# ACme.net
KiCad netlist of a schematic drawn in EAGLE
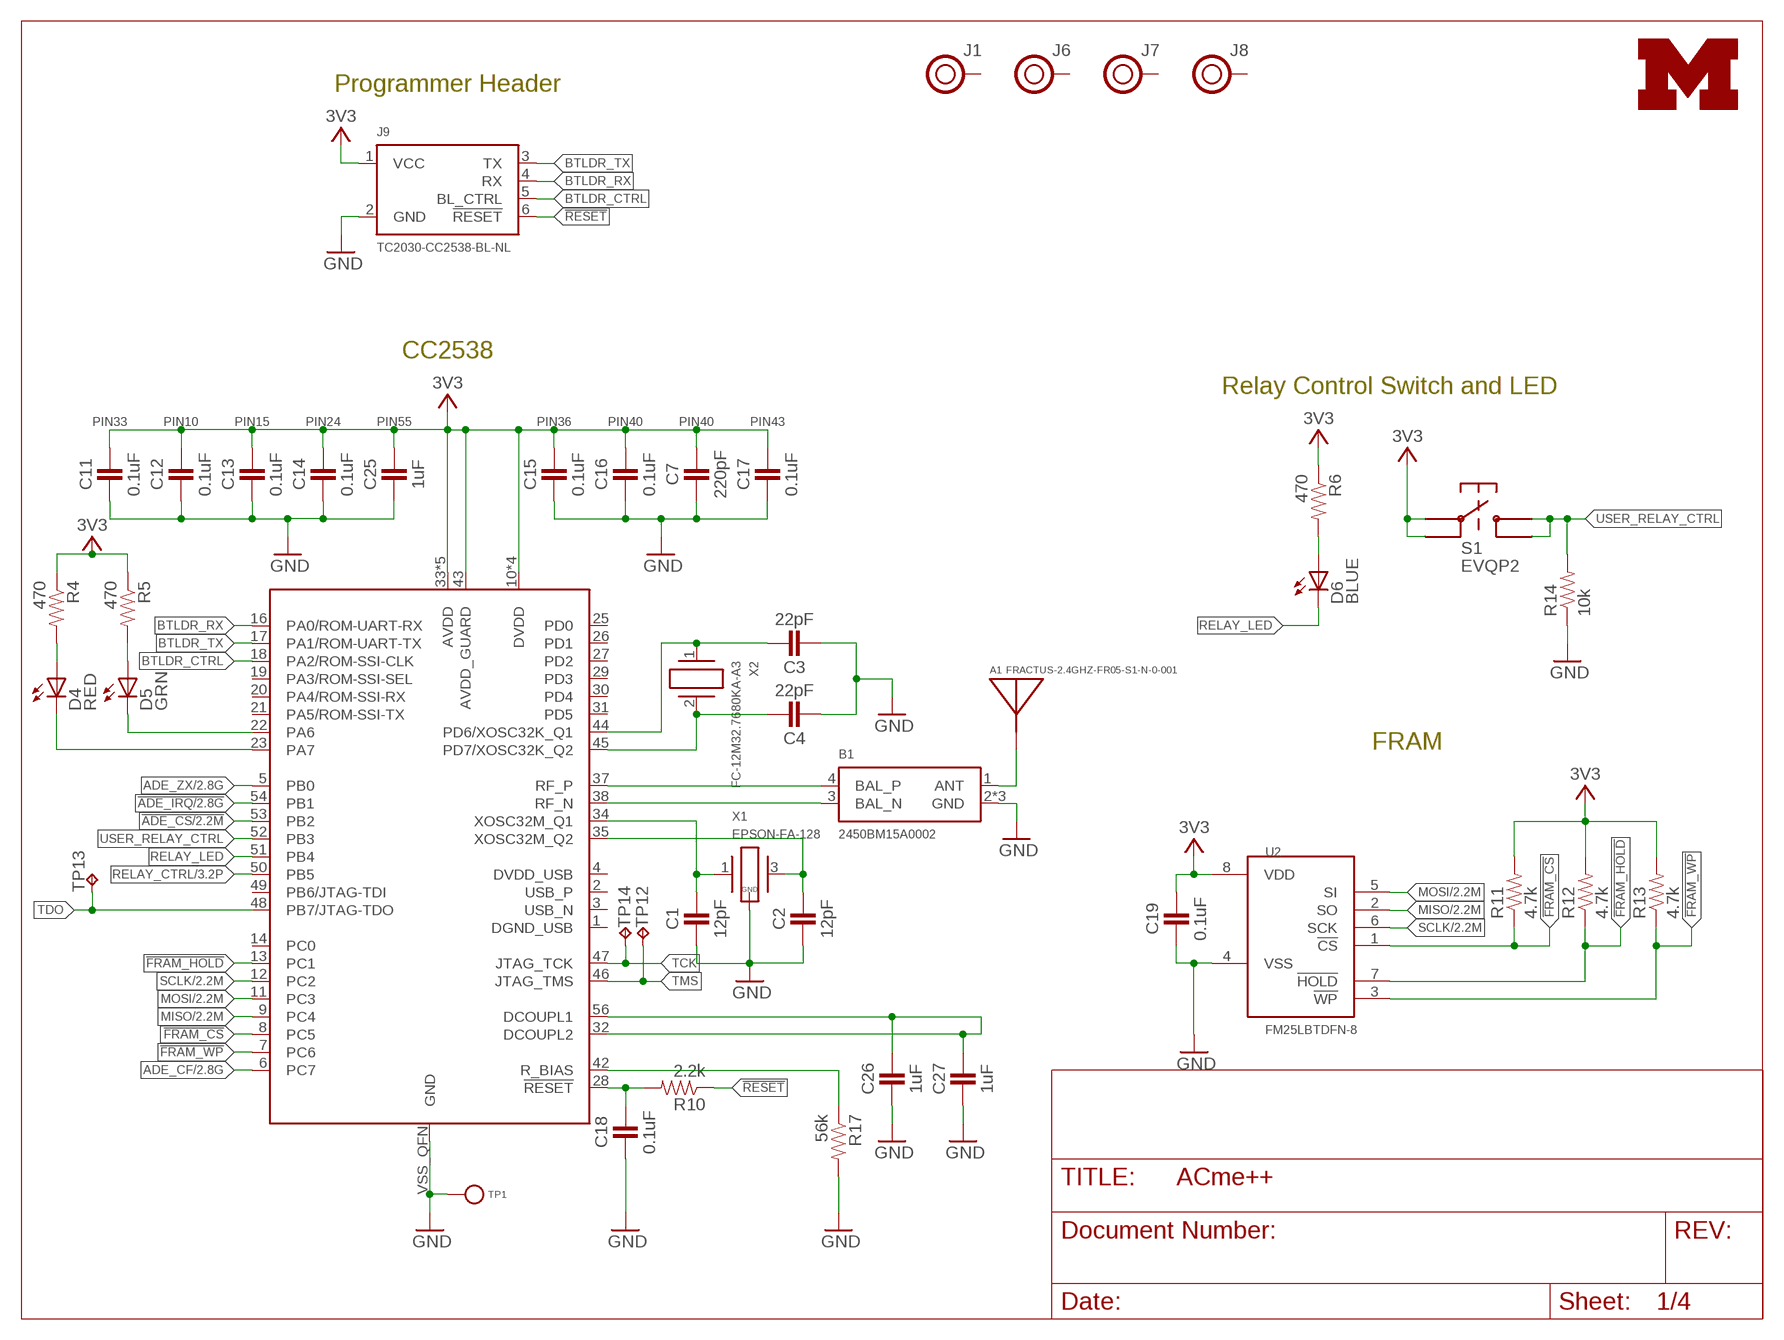
[diagram p0: schematic, sheet 1]
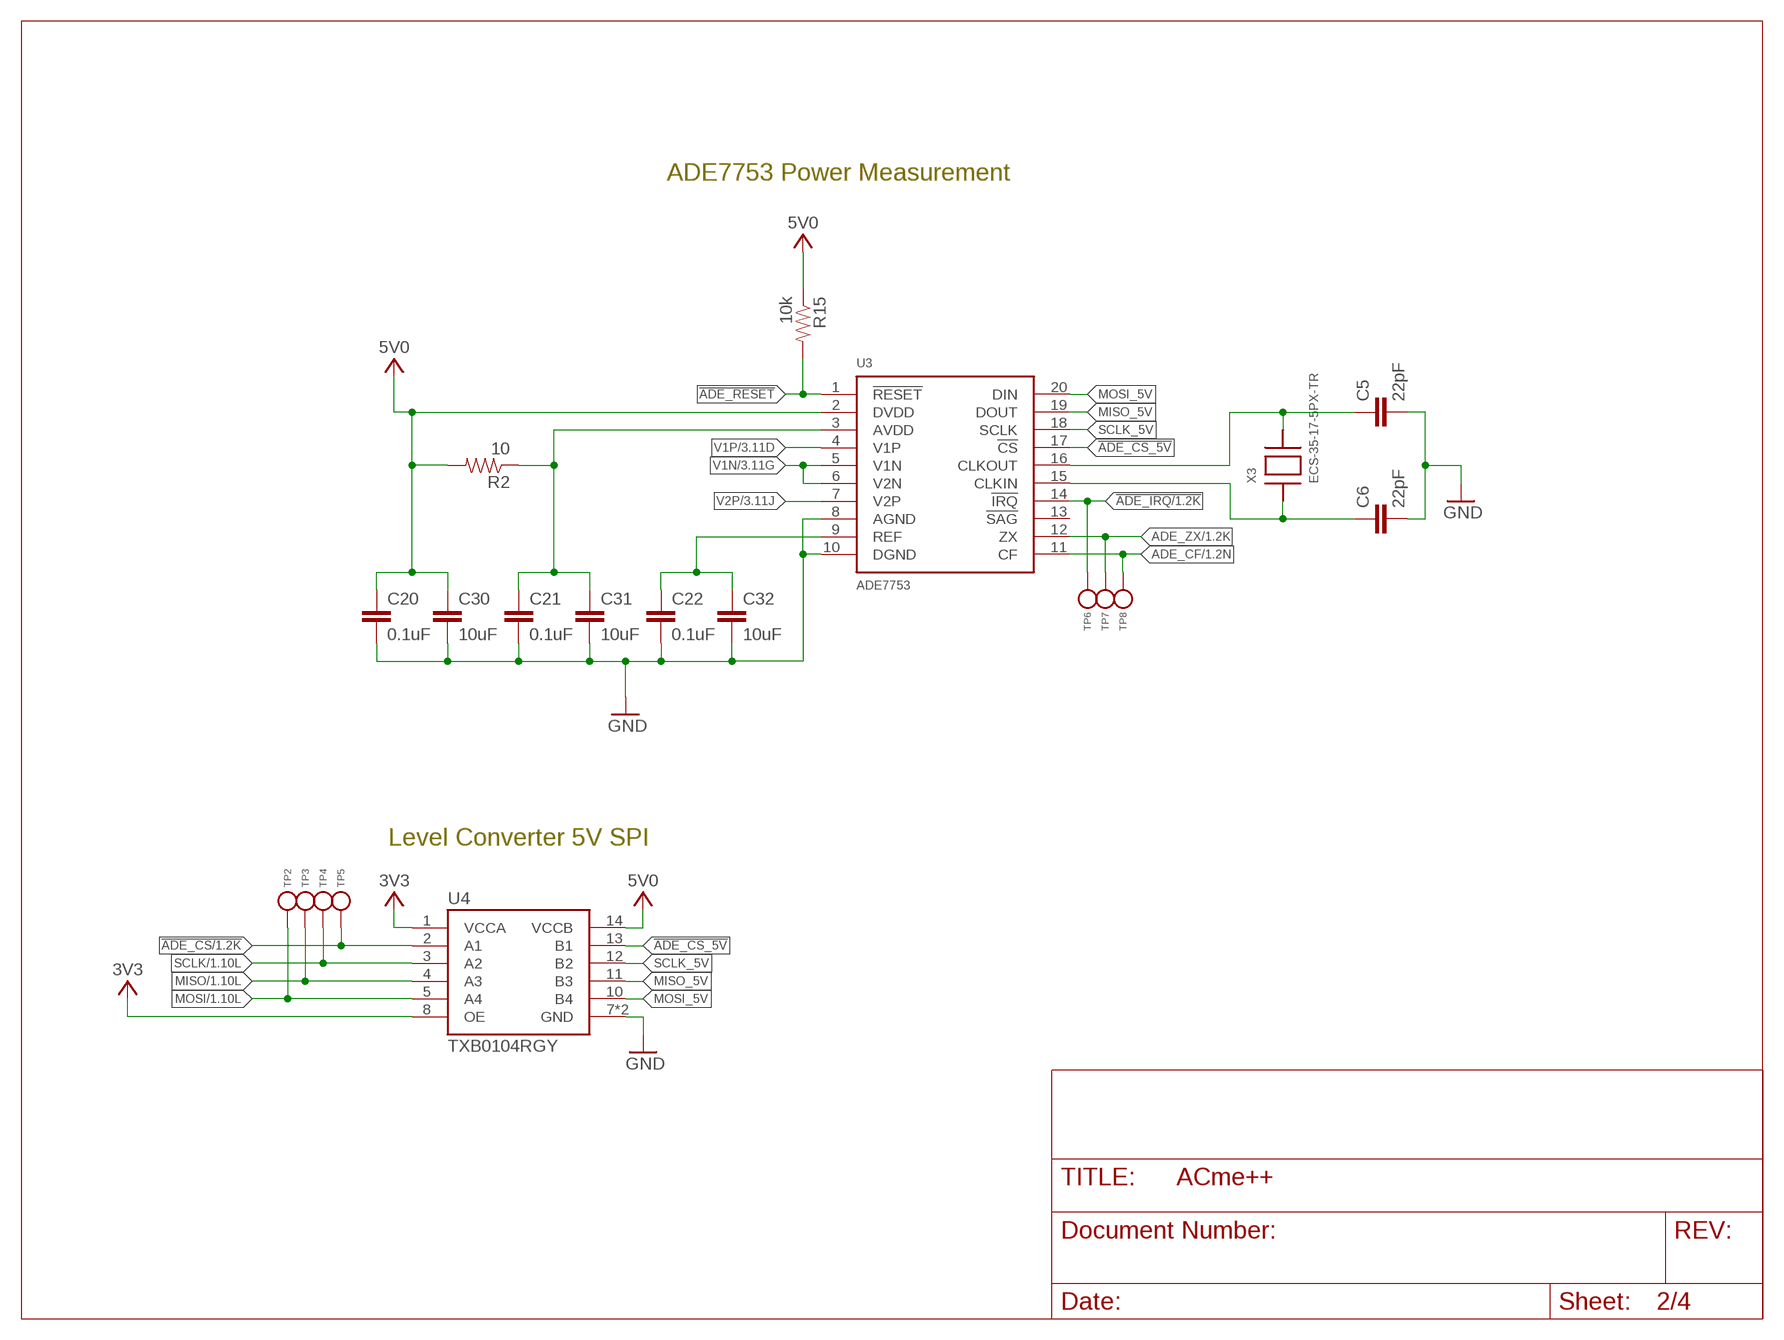
[diagram p1: schematic, sheet 2]
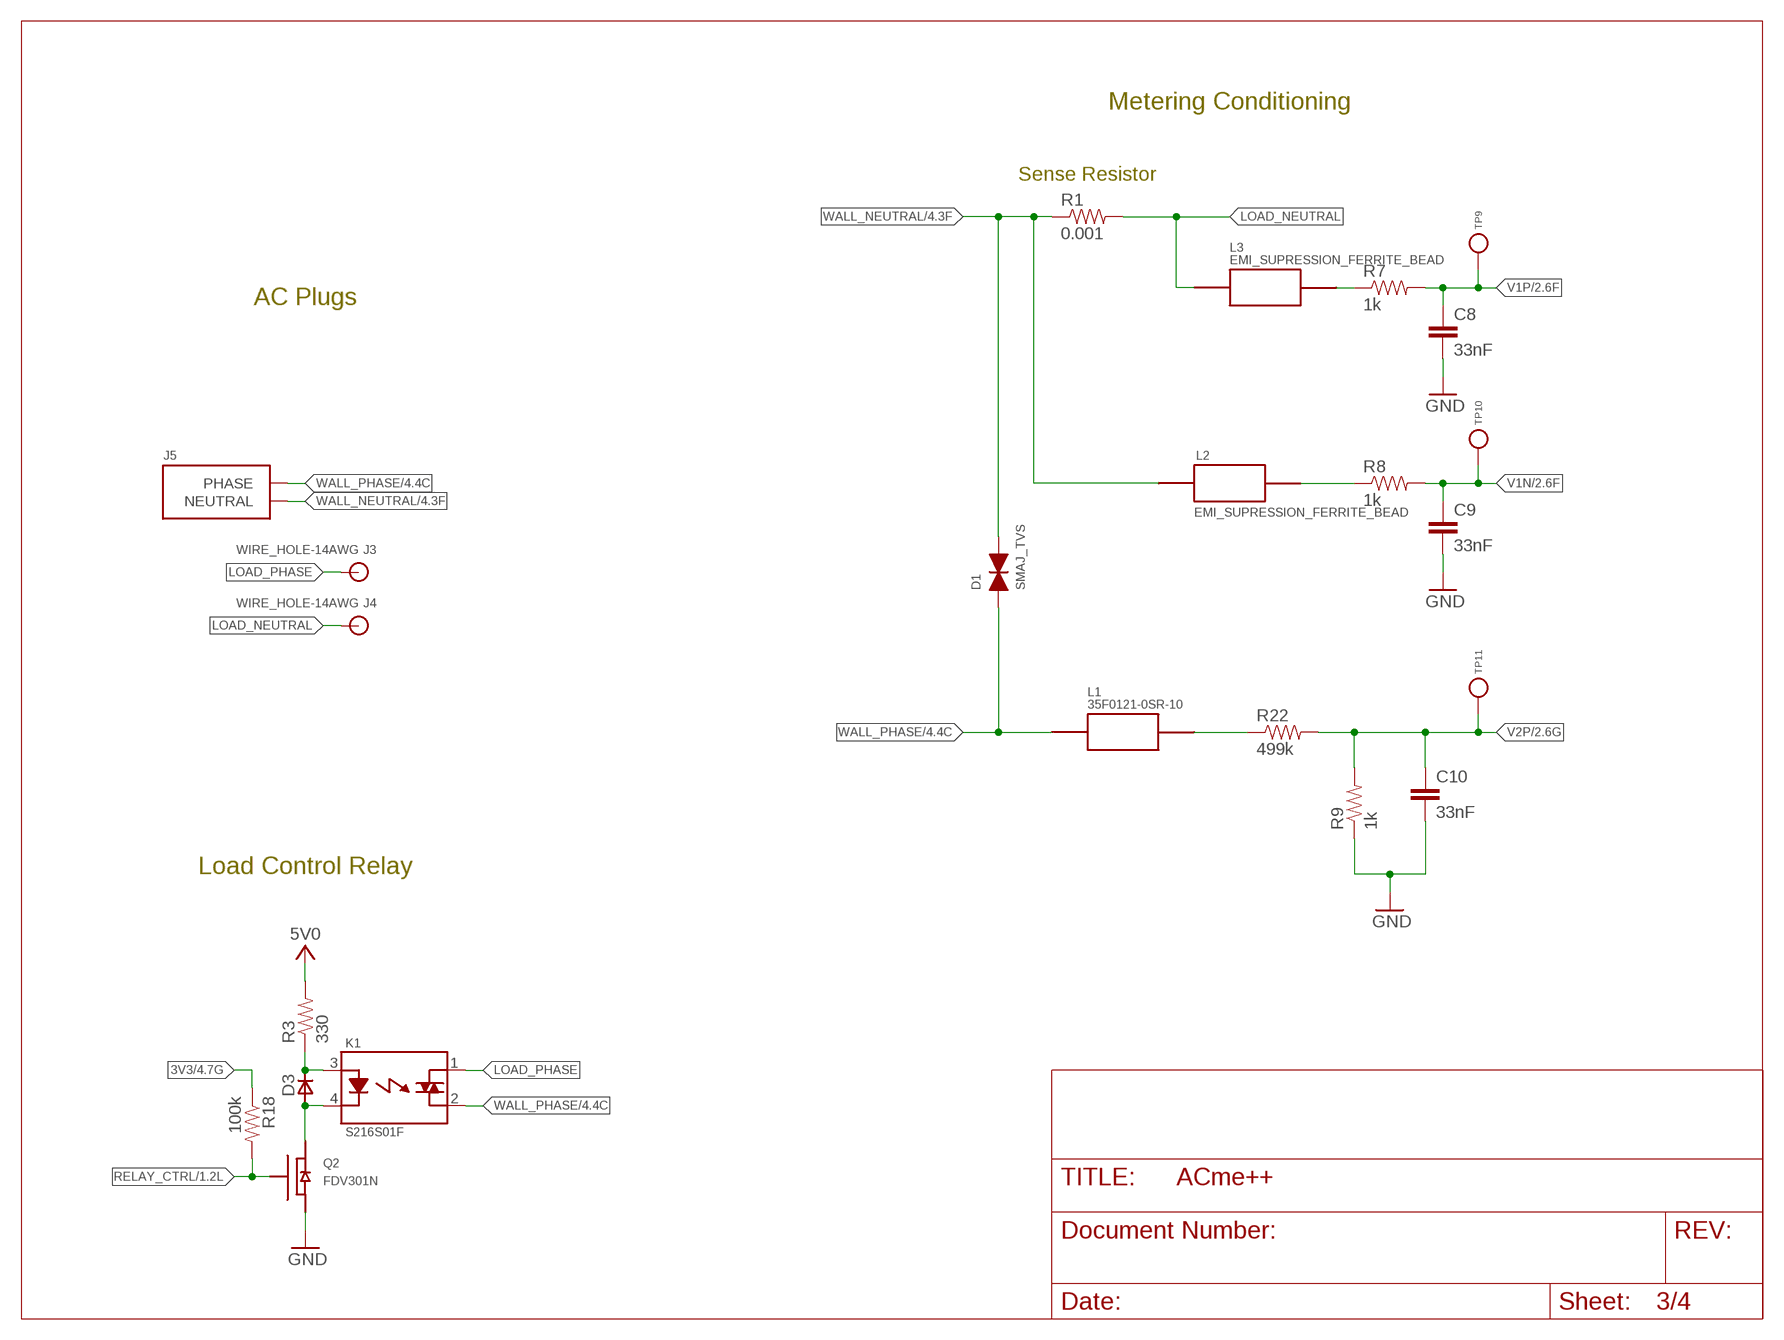
[diagram p2: schematic, sheet 3]
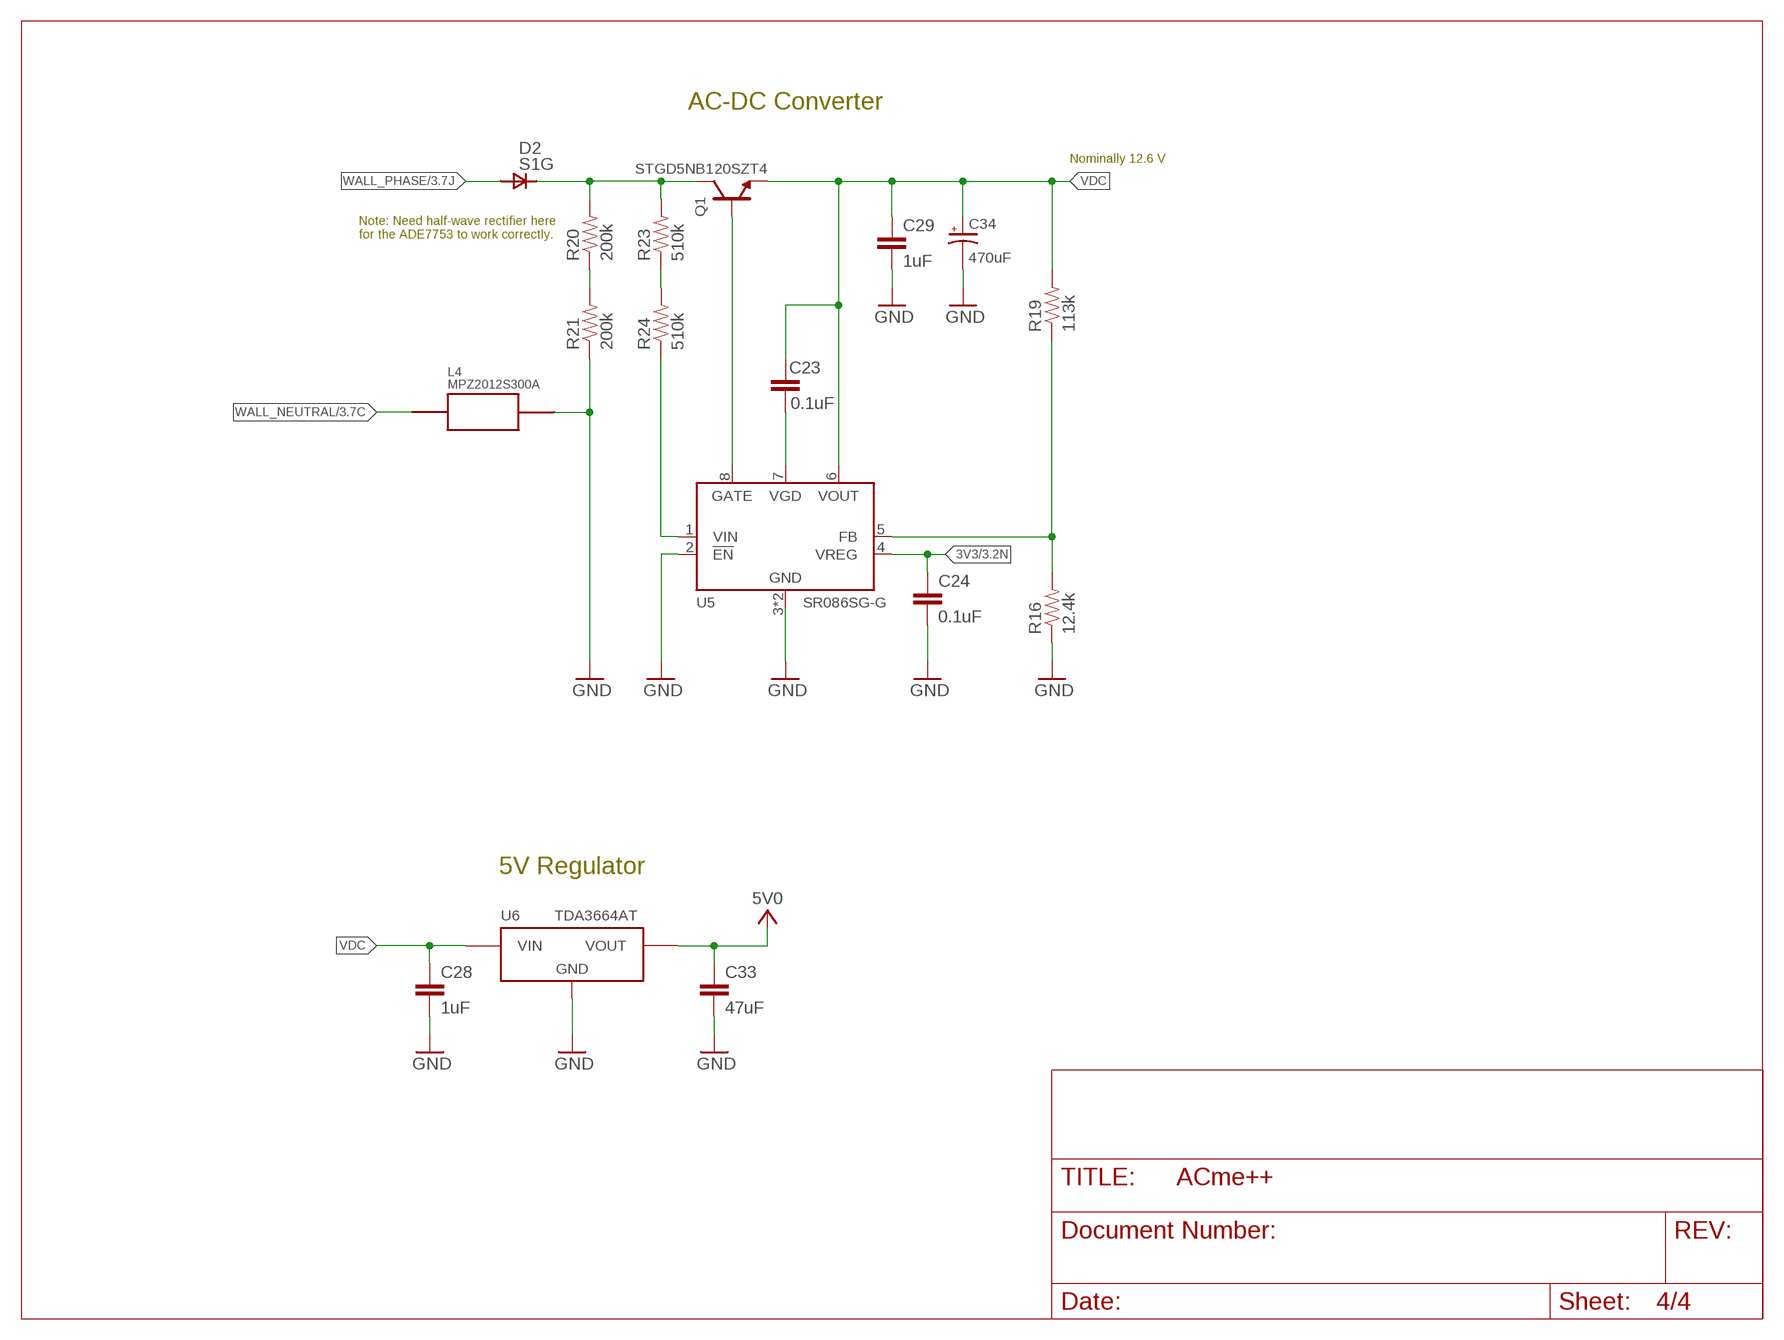
[diagram p3: schematic, sheet 4]

(export (version "E")
  (design (tool "Eeschema 10.0.6"))
  (components
    (comp (ref "A1")
      (value "FRACTUS-2.4GHZ-FR05-S1-N-0-001")
      (footprint "eagle-import:FRACTUS-ANTENNA-FR05-S1-N-0-001")
      (libsource (lib "eagle-import") (part "FRACTUS-2.4GHZ-FR05-S1-N-0-001"))
    )
    (comp (ref "B1")
      (value "2450BM15A0002")
      (footprint "eagle-import:2450BM")
      (libsource (lib "eagle-import") (part "2450BM15A0002"))
    )
    (comp (ref "C1")
      (value "12pF")
      (footprint "eagle-import:0402_CAP")
      (libsource (lib "eagle-import") (part "CAPACITOR"))
    )
    (comp (ref "C2")
      (value "12pF")
      (footprint "eagle-import:0402_CAP")
      (libsource (lib "eagle-import") (part "CAPACITOR"))
    )
    (comp (ref "C3")
      (value "22pF")
      (footprint "eagle-import:0402_CAP")
      (libsource (lib "eagle-import") (part "CAPACITOR"))
    )
    (comp (ref "C4")
      (value "22pF")
      (footprint "eagle-import:0402_CAP")
      (libsource (lib "eagle-import") (part "CAPACITOR"))
    )
    (comp (ref "C7")
      (value "220pF")
      (footprint "eagle-import:0402_CAP")
      (libsource (lib "eagle-import") (part "CAPACITOR"))
    )
    (comp (ref "C11")
      (value "0.1uF")
      (footprint "eagle-import:0402_CAP")
      (libsource (lib "eagle-import") (part "CAPACITOR"))
    )
    (comp (ref "C12")
      (value "0.1uF")
      (footprint "eagle-import:0402_CAP")
      (libsource (lib "eagle-import") (part "CAPACITOR"))
    )
    (comp (ref "C13")
      (value "0.1uF")
      (footprint "eagle-import:0402_CAP")
      (libsource (lib "eagle-import") (part "CAPACITOR"))
    )
    (comp (ref "C14")
      (value "0.1uF")
      (footprint "eagle-import:0402_CAP")
      (libsource (lib "eagle-import") (part "CAPACITOR"))
    )
    (comp (ref "C15")
      (value "0.1uF")
      (footprint "eagle-import:0402_CAP")
      (libsource (lib "eagle-import") (part "CAPACITOR"))
    )
    (comp (ref "C16")
      (value "0.1uF")
      (footprint "eagle-import:0402_CAP")
      (libsource (lib "eagle-import") (part "CAPACITOR"))
    )
    (comp (ref "C17")
      (value "0.1uF")
      (footprint "eagle-import:0402_CAP")
      (libsource (lib "eagle-import") (part "CAPACITOR"))
    )
    (comp (ref "C18")
      (value "0.1uF")
      (footprint "eagle-import:0402_CAP")
      (libsource (lib "eagle-import") (part "CAPACITOR"))
    )
    (comp (ref "C19")
      (value "0.1uF")
      (footprint "eagle-import:0402_CAP")
      (libsource (lib "eagle-import") (part "CAPACITOR"))
    )
    (comp (ref "C25")
      (value "1uF")
      (footprint "eagle-import:0402_CAP")
      (libsource (lib "eagle-import") (part "CAPACITOR"))
    )
    (comp (ref "C26")
      (value "1uF")
      (footprint "eagle-import:0402_CAP")
      (libsource (lib "eagle-import") (part "CAPACITOR"))
    )
    (comp (ref "C27")
      (value "1uF")
      (footprint "eagle-import:0402_CAP")
      (libsource (lib "eagle-import") (part "CAPACITOR"))
    )
    (comp (ref "D4")
      (value "RED")
      (footprint "eagle-import:LED-0603")
      (libsource (lib "eagle-import") (part "LED0603"))
    )
    (comp (ref "D5")
      (value "GRN")
      (footprint "eagle-import:LED-0603")
      (libsource (lib "eagle-import") (part "LED0603"))
    )
    (comp (ref "D6")
      (value "BLUE")
      (footprint "eagle-import:LED-0603")
      (libsource (lib "eagle-import") (part "LED0603"))
    )
    (comp (ref "J1")
      (value "HOLE")
      (footprint "eagle-import:HOLE-0.125")
      (libsource (lib "eagle-import") (part "HOLE"))
    )
    (comp (ref "J6")
      (value "HOLE")
      (footprint "eagle-import:HOLE-0.125")
      (libsource (lib "eagle-import") (part "HOLE"))
    )
    (comp (ref "J7")
      (value "HOLE")
      (footprint "eagle-import:HOLE-0.125")
      (libsource (lib "eagle-import") (part "HOLE"))
    )
    (comp (ref "J8")
      (value "HOLE")
      (footprint "eagle-import:HOLE-0.125")
      (libsource (lib "eagle-import") (part "HOLE"))
    )
    (comp (ref "J9")
      (value "TC2030-CC2538-BL-NL")
      (footprint "eagle-import:TC2030-IDC-NL")
      (libsource (lib "eagle-import") (part "TC2030-CC2538-BL-NL"))
    )
    (comp (ref "R4")
      (value "470")
      (footprint "eagle-import:0402_RES")
      (libsource (lib "eagle-import") (part "passives_RESISTOR"))
    )
    (comp (ref "R5")
      (value "470")
      (footprint "eagle-import:0402_RES")
      (libsource (lib "eagle-import") (part "passives_RESISTOR"))
    )
    (comp (ref "R6")
      (value "470")
      (footprint "eagle-import:0402_RES")
      (libsource (lib "eagle-import") (part "passives_RESISTOR"))
    )
    (comp (ref "R10")
      (value "2.2k")
      (footprint "eagle-import:0402_RES")
      (libsource (lib "eagle-import") (part "passives_RESISTOR"))
    )
    (comp (ref "R11")
      (value "4.7k")
      (footprint "eagle-import:0402_RES")
      (libsource (lib "eagle-import") (part "passives_RESISTOR"))
    )
    (comp (ref "R12")
      (value "4.7k")
      (footprint "eagle-import:0402_RES")
      (libsource (lib "eagle-import") (part "passives_RESISTOR"))
    )
    (comp (ref "R13")
      (value "4.7k")
      (footprint "eagle-import:0402_RES")
      (libsource (lib "eagle-import") (part "passives_RESISTOR"))
    )
    (comp (ref "R14")
      (value "10k")
      (footprint "eagle-import:0603-RES")
      (libsource (lib "eagle-import") (part "RESISTOR0603-RES"))
    )
    (comp (ref "R17")
      (value "56k")
      (footprint "eagle-import:0402_RES")
      (libsource (lib "eagle-import") (part "passives_RESISTOR"))
    )
    (comp (ref "S1")
      (value "EVQP2")
      (footprint "eagle-import:EVQP2")
      (libsource (lib "eagle-import") (part "EVQP2"))
    )
    (comp (ref "TP1")
      (value "TEST_POINT_0.040IN")
      (footprint "eagle-import:TESTPOINT_0.040IN")
      (libsource (lib "eagle-import") (part "TEST_POINT_0.040IN"))
    )
    (comp (ref "TP12")
      (value "TPTP09SQ")
      (footprint "eagle-import:TP09SQ")
      (libsource (lib "eagle-import") (part "TPTP09SQ"))
    )
    (comp (ref "TP13")
      (value "TPTP09SQ")
      (footprint "eagle-import:TP09SQ")
      (libsource (lib "eagle-import") (part "TPTP09SQ"))
    )
    (comp (ref "TP14")
      (value "TPTP09SQ")
      (footprint "eagle-import:TP09SQ")
      (libsource (lib "eagle-import") (part "TPTP09SQ"))
    )
    (comp (ref "U$3")
      (value "UMICH_SOLID_MEDIUM")
      (footprint "eagle-import:UMICH_SOLID_200MIL")
      (libsource (lib "eagle-import") (part "UMICH_SOLID_MEDIUM"))
    )
    (comp (ref "U1")
      (value "CC2538")
      (footprint "eagle-import:S-PVQFN-N56")
      (libsource (lib "eagle-import") (part "CC2538"))
    )
    (comp (ref "U2")
      (value "FM25LBTDFN-8")
      (footprint "eagle-import:TDFN-8")
      (libsource (lib "eagle-import") (part "FM25LBTDFN-8"))
    )
    (comp (ref "X1")
      (value "EPSON-FA-128")
      (footprint "eagle-import:FA-128")
      (libsource (lib "eagle-import") (part "EPSON-FA-128"))
    )
    (comp (ref "X2")
      (value "FC-12M32.7680KA-A3")
      (footprint "eagle-import:FC-12M")
      (libsource (lib "eagle-import") (part "FC-12M32.7680KA-A3"))
    )
    (comp (ref "C5")
      (value "22pF")
      (footprint "eagle-import:0603-CAP")
      (libsource (lib "eagle-import") (part "CAP0603-CAP"))
    )
    (comp (ref "C6")
      (value "22pF")
      (footprint "eagle-import:0603-CAP")
      (libsource (lib "eagle-import") (part "CAP0603-CAP"))
    )
    (comp (ref "C20")
      (value "0.1uF")
      (footprint "eagle-import:0603-CAP")
      (libsource (lib "eagle-import") (part "CAP0603-CAP"))
    )
    (comp (ref "C21")
      (value "0.1uF")
      (footprint "eagle-import:0603-CAP")
      (libsource (lib "eagle-import") (part "CAP0603-CAP"))
    )
    (comp (ref "C22")
      (value "0.1uF")
      (footprint "eagle-import:0603-CAP")
      (libsource (lib "eagle-import") (part "CAP0603-CAP"))
    )
    (comp (ref "C30")
      (value "10uF")
      (footprint "eagle-import:0603-CAP")
      (libsource (lib "eagle-import") (part "CAP0603-CAP"))
    )
    (comp (ref "C31")
      (value "10uF")
      (footprint "eagle-import:0603-CAP")
      (libsource (lib "eagle-import") (part "CAP0603-CAP"))
    )
    (comp (ref "C32")
      (value "10uF")
      (footprint "eagle-import:0603-CAP")
      (libsource (lib "eagle-import") (part "CAP0603-CAP"))
    )
    (comp (ref "R2")
      (value "10")
      (footprint "eagle-import:0603-RES")
      (libsource (lib "eagle-import") (part "RESISTOR0603-RES"))
    )
    (comp (ref "R15")
      (value "10k")
      (footprint "eagle-import:0603-RES")
      (libsource (lib "eagle-import") (part "RESISTOR0603-RES"))
    )
    (comp (ref "TP2")
      (value "TEST_POINT_0.040IN")
      (footprint "eagle-import:TESTPOINT_0.040IN")
      (libsource (lib "eagle-import") (part "TEST_POINT_0.040IN"))
    )
    (comp (ref "TP3")
      (value "TEST_POINT_0.040IN")
      (footprint "eagle-import:TESTPOINT_0.040IN")
      (libsource (lib "eagle-import") (part "TEST_POINT_0.040IN"))
    )
    (comp (ref "TP4")
      (value "TEST_POINT_0.040IN")
      (footprint "eagle-import:TESTPOINT_0.040IN")
      (libsource (lib "eagle-import") (part "TEST_POINT_0.040IN"))
    )
    (comp (ref "TP5")
      (value "TEST_POINT_0.040IN")
      (footprint "eagle-import:TESTPOINT_0.040IN")
      (libsource (lib "eagle-import") (part "TEST_POINT_0.040IN"))
    )
    (comp (ref "TP6")
      (value "TEST_POINT_0.040IN")
      (footprint "eagle-import:TESTPOINT_0.040IN")
      (libsource (lib "eagle-import") (part "TEST_POINT_0.040IN"))
    )
    (comp (ref "TP7")
      (value "TEST_POINT_0.040IN")
      (footprint "eagle-import:TESTPOINT_0.040IN")
      (libsource (lib "eagle-import") (part "TEST_POINT_0.040IN"))
    )
    (comp (ref "TP8")
      (value "TEST_POINT_0.040IN")
      (footprint "eagle-import:TESTPOINT_0.040IN")
      (libsource (lib "eagle-import") (part "TEST_POINT_0.040IN"))
    )
    (comp (ref "U3")
      (value "ADE7753")
      (footprint "eagle-import:SSOP-20")
      (fields (field (name "MOUSER") " 584-ADE7753ARSZR "))
      (libsource (lib "eagle-import") (part "ADE7753"))
    )
    (comp (ref "U4")
      (value "TXB0104RGY")
      (footprint "eagle-import:S-PVQFN-N14")
      (libsource (lib "eagle-import") (part "TXB0104RGY"))
    )
    (comp (ref "X3")
      (value "ECS-35-17-5PX-TR")
      (footprint "eagle-import:CSM-7X")
      (libsource (lib "eagle-import") (part "ECS-35-17-5PX-TR"))
    )
    (comp (ref "C23")
      (value "0.1uF")
      (footprint "eagle-import:0603-CAP")
      (libsource (lib "eagle-import") (part "CAP0603-CAP"))
    )
    (comp (ref "C24")
      (value "0.1uF")
      (footprint "eagle-import:0603-CAP")
      (libsource (lib "eagle-import") (part "CAP0603-CAP"))
    )
    (comp (ref "C28")
      (value "1uF")
      (footprint "eagle-import:0603-CAP")
      (libsource (lib "eagle-import") (part "CAP0603-CAP"))
    )
    (comp (ref "C29")
      (value "1uF")
      (footprint "eagle-import:1206")
      (libsource (lib "eagle-import") (part "CAP1206"))
    )
    (comp (ref "C33")
      (value "47uF")
      (footprint "eagle-import:1206")
      (libsource (lib "eagle-import") (part "CAP1206"))
    )
    (comp (ref "C34")
      (value "470uF")
      (footprint "eagle-import:CAP_SM_10MM")
      (libsource (lib "eagle-import") (part "CAP_EEE-FP1E471AP"))
    )
    (comp (ref "D2")
      (value "S1G")
      (footprint "eagle-import:DO-214AC")
      (libsource (lib "eagle-import") (part "S1G"))
    )
    (comp (ref "L4")
      (value "MPZ2012S300A")
      (footprint "eagle-import:0805_RESISTOR")
      (libsource (lib "eagle-import") (part "MPZ2012S300A"))
    )
    (comp (ref "Q1")
      (value "STGD5NB120SZT4")
      (footprint "eagle-import:DPAK")
      (libsource (lib "eagle-import") (part "STGD5NB120SZT4"))
    )
    (comp (ref "R16")
      (value "12.4k")
      (footprint "eagle-import:0603-RES")
      (libsource (lib "eagle-import") (part "SparkFun-Resistors_RESISTOR0603-RES"))
    )
    (comp (ref "R19")
      (value "113k")
      (footprint "eagle-import:0603-RES")
      (libsource (lib "eagle-import") (part "SparkFun-Resistors_RESISTOR0603-RES"))
    )
    (comp (ref "R20")
      (value "200k")
      (footprint "eagle-import:1206")
      (libsource (lib "eagle-import") (part "SparkFun-Resistors_RESISTOR1206"))
    )
    (comp (ref "R21")
      (value "200k")
      (footprint "eagle-import:1206")
      (libsource (lib "eagle-import") (part "SparkFun-Resistors_RESISTOR1206"))
    )
    (comp (ref "R23")
      (value "510k")
      (footprint "eagle-import:1206")
      (libsource (lib "eagle-import") (part "SparkFun-Resistors_RESISTOR1206"))
    )
    (comp (ref "R24")
      (value "510k")
      (footprint "eagle-import:1206")
      (libsource (lib "eagle-import") (part "SparkFun-Resistors_RESISTOR1206"))
    )
    (comp (ref "U5")
      (value "SR086SG-G")
      (footprint "eagle-import:SR086")
      (libsource (lib "eagle-import") (part "SR086SG-G"))
    )
    (comp (ref "U6")
      (value "TDA3664AT")
      (footprint "eagle-import:SOIC_8")
      (libsource (lib "eagle-import") (part "TDA3664AT"))
    )
    (comp (ref "C8")
      (value "33nF")
      (footprint "eagle-import:0805")
      (libsource (lib "eagle-import") (part "CAP0805"))
    )
    (comp (ref "C9")
      (value "33nF")
      (footprint "eagle-import:0805")
      (libsource (lib "eagle-import") (part "CAP0805"))
    )
    (comp (ref "C10")
      (value "33nF")
      (footprint "eagle-import:0805")
      (libsource (lib "eagle-import") (part "CAP0805"))
    )
    (comp (ref "D1")
      (value "SMAJ_TVS")
      (footprint "eagle-import:DO214_TVS")
      (libsource (lib "eagle-import") (part "SMAJ_TVS"))
    )
    (comp (ref "D3")
      (value "DIODE_MMBD914")
      (footprint "eagle-import:SOT-23")
      (libsource (lib "eagle-import") (part "DIODE_MMBD914"))
    )
    (comp (ref "J3")
      (value "WIRE_HOLE-14AWG")
      (footprint "eagle-import:WIRE_HOLE-14AWG")
      (libsource (lib "eagle-import") (part "WIRE_HOLE-14AWG"))
    )
    (comp (ref "J4")
      (value "WIRE_HOLE-14AWG")
      (footprint "eagle-import:WIRE_HOLE-14AWG")
      (libsource (lib "eagle-import") (part "WIRE_HOLE-14AWG"))
    )
    (comp (ref "J5")
      (value "AC-PLUG-2")
      (footprint "eagle-import:AC_MALE_PINS_2")
      (libsource (lib "eagle-import") (part "AC-PLUG-2"))
    )
    (comp (ref "K1")
      (value "S216S01F")
      (footprint "eagle-import:RELAY_SX16S0X")
      (libsource (lib "eagle-import") (part "S216S01F"))
    )
    (comp (ref "L1")
      (value "35F0121-0SR-10")
      (footprint "eagle-import:35F0102")
      (libsource (lib "eagle-import") (part "35F0121-0SR-10"))
    )
    (comp (ref "L2")
      (value "EMI_SUPRESSION_FERRITE_BEAD")
      (footprint "eagle-import:L1806")
      (libsource (lib "eagle-import") (part "EMI_SUPRESSION_FERRITE_BEAD"))
    )
    (comp (ref "L3")
      (value "EMI_SUPRESSION_FERRITE_BEAD")
      (footprint "eagle-import:L1806")
      (libsource (lib "eagle-import") (part "EMI_SUPRESSION_FERRITE_BEAD"))
    )
    (comp (ref "Q2")
      (value "FDV301N")
      (footprint "eagle-import:SOT-23")
      (libsource (lib "eagle-import") (part "FDV301N"))
    )
    (comp (ref "R1")
      (value "0.001")
      (footprint "eagle-import:R2512")
      (libsource (lib "eagle-import") (part "SparkFun-Resistors_RESISTOR2512"))
    )
    (comp (ref "R3")
      (value "330")
      (footprint "eagle-import:0805")
      (libsource (lib "eagle-import") (part "RESISTOR0805-RES"))
    )
    (comp (ref "R7")
      (value "1k")
      (footprint "eagle-import:0805")
      (libsource (lib "eagle-import") (part "RESISTOR0805-RES"))
    )
    (comp (ref "R8")
      (value "1k")
      (footprint "eagle-import:0805")
      (libsource (lib "eagle-import") (part "RESISTOR0805-RES"))
    )
    (comp (ref "R9")
      (value "1k")
      (footprint "eagle-import:0805")
      (libsource (lib "eagle-import") (part "RESISTOR0805-RES"))
    )
    (comp (ref "R18")
      (value "100k")
      (footprint "eagle-import:0603-RES")
      (libsource (lib "eagle-import") (part "RESISTOR0603-RES"))
    )
    (comp (ref "R22")
      (value "499k")
      (footprint "eagle-import:0805")
      (libsource (lib "eagle-import") (part "RESISTOR0805-RES"))
    )
    (comp (ref "TP9")
      (value "TEST_POINT_0.040IN")
      (footprint "eagle-import:TESTPOINT_0.040IN")
      (libsource (lib "eagle-import") (part "TEST_POINT_0.040IN"))
    )
    (comp (ref "TP10")
      (value "TEST_POINT_0.040IN")
      (footprint "eagle-import:TESTPOINT_0.040IN")
      (libsource (lib "eagle-import") (part "TEST_POINT_0.040IN"))
    )
    (comp (ref "TP11")
      (value "TEST_POINT_0.040IN")
      (footprint "eagle-import:TESTPOINT_0.040IN")
      (libsource (lib "eagle-import") (part "TEST_POINT_0.040IN"))
    )
  )
  (nets
    (net (code "1") (name "3V3") (class "Default")
      (node (ref "C11") (pin "1") (pinfunction "1_1") (pintype "bidirectional"))
      (node (ref "C12") (pin "1") (pinfunction "1_1") (pintype "bidirectional"))
      (node (ref "C13") (pin "1") (pinfunction "1_1") (pintype "bidirectional"))
      (node (ref "C14") (pin "1") (pinfunction "1_1") (pintype "bidirectional"))
      (node (ref "C15") (pin "1") (pinfunction "1_1") (pintype "bidirectional"))
      (node (ref "C16") (pin "1") (pinfunction "1_1") (pintype "bidirectional"))
      (node (ref "C17") (pin "1") (pinfunction "1_1") (pintype "bidirectional"))
      (node (ref "C19") (pin "1") (pinfunction "1_1") (pintype "bidirectional"))
      (node (ref "C24") (pin "1") (pinfunction "1_1") (pintype "passive"))
      (node (ref "C25") (pin "1") (pinfunction "1_1") (pintype "bidirectional"))
      (node (ref "C7") (pin "1") (pinfunction "1_1") (pintype "bidirectional"))
      (node (ref "J9") (pin "1") (pinfunction "VCC_1") (pintype "bidirectional"))
      (node (ref "R11") (pin "2") (pinfunction "2_2") (pintype "passive"))
      (node (ref "R12") (pin "2") (pinfunction "2_2") (pintype "passive"))
      (node (ref "R13") (pin "2") (pinfunction "2_2") (pintype "passive"))
      (node (ref "R18") (pin "1") (pinfunction "1_1") (pintype "passive"))
      (node (ref "R4") (pin "1") (pinfunction "1_1") (pintype "passive"))
      (node (ref "R5") (pin "1") (pinfunction "1_1") (pintype "passive"))
      (node (ref "R6") (pin "1") (pinfunction "1_1") (pintype "passive"))
      (node (ref "S1") (pin "P$1") (pinfunction "P$1_P$1") (pintype "passive"))
      (node (ref "S1") (pin "P$3") (pinfunction "P$3_P$3") (pintype "passive"))
      (node (ref "U1") (pin "10") (pinfunction "DVDD_10") (pintype "bidirectional"))
      (node (ref "U1") (pin "15") (pinfunction "DVDD_15") (pintype "bidirectional"))
      (node (ref "U1") (pin "24") (pinfunction "DVDD_24") (pintype "bidirectional"))
      (node (ref "U1") (pin "33") (pinfunction "AVDD_33") (pintype "bidirectional"))
      (node (ref "U1") (pin "36") (pinfunction "AVDD_36") (pintype "bidirectional"))
      (node (ref "U1") (pin "39") (pinfunction "AVDD_39") (pintype "bidirectional"))
      (node (ref "U1") (pin "40") (pinfunction "AVDD_40") (pintype "bidirectional"))
      (node (ref "U1") (pin "41") (pinfunction "AVDD_41") (pintype "bidirectional"))
      (node (ref "U1") (pin "43") (pinfunction "AVDD_GUARD_43") (pintype "bidirectional"))
      (node (ref "U1") (pin "55") (pinfunction "DVDD_55") (pintype "bidirectional"))
      (node (ref "U2") (pin "8") (pinfunction "VDD_8") (pintype "bidirectional"))
      (node (ref "U4") (pin "1") (pinfunction "VCCA_1") (pintype "bidirectional"))
      (node (ref "U4") (pin "8") (pinfunction "OE_8") (pintype "bidirectional"))
      (node (ref "U5") (pin "4") (pinfunction "VREG_4") (pintype "bidirectional"))
    )
    (net (code "2") (name "5V0") (class "Default")
      (node (ref "C20") (pin "1") (pinfunction "1_1") (pintype "passive"))
      (node (ref "C30") (pin "1") (pinfunction "1_1") (pintype "passive"))
      (node (ref "C33") (pin "1") (pinfunction "1_1") (pintype "passive"))
      (node (ref "R15") (pin "1") (pinfunction "1_1") (pintype "passive"))
      (node (ref "R2") (pin "2") (pinfunction "2_2") (pintype "passive"))
      (node (ref "R3") (pin "2") (pinfunction "2_2") (pintype "passive"))
      (node (ref "U3") (pin "2") (pinfunction "DVDD_2") (pintype "bidirectional"))
      (node (ref "U4") (pin "14") (pinfunction "VCCB_14") (pintype "bidirectional"))
      (node (ref "U6") (pin "1") (pinfunction "VOUT_1") (pintype "bidirectional"))
    )
    (net (code "3") (name "ADE_CF") (class "Default")
      (node (ref "TP8") (pin "TESTPOINT") (pinfunction "TESTPOINT_TESTPOINT") (pintype "bidirectional"))
      (node (ref "U1") (pin "6") (pinfunction "PC7_6") (pintype "bidirectional"))
      (node (ref "U3") (pin "11") (pinfunction "CF_11") (pintype "bidirectional"))
    )
    (net (code "4") (name "ADE_ZX") (class "Default")
      (node (ref "TP7") (pin "TESTPOINT") (pinfunction "TESTPOINT_TESTPOINT") (pintype "bidirectional"))
      (node (ref "U1") (pin "5") (pinfunction "PB0_5") (pintype "bidirectional"))
      (node (ref "U3") (pin "12") (pinfunction "ZX_12") (pintype "bidirectional"))
    )
    (net (code "5") (name "BTLDR_CTRL") (class "Default")
      (node (ref "J9") (pin "5") (pinfunction "BL_CTRL_5") (pintype "bidirectional"))
      (node (ref "U1") (pin "18") (pinfunction "PA2/ROM-SSI-CLK_18") (pintype "bidirectional"))
    )
    (net (code "6") (name "BTLDR_RX") (class "Default")
      (node (ref "J9") (pin "4") (pinfunction "RX_4") (pintype "bidirectional"))
      (node (ref "U1") (pin "16") (pinfunction "PA0/ROM-UART-RX_16") (pintype "bidirectional"))
    )
    (net (code "7") (name "BTLDR_TX") (class "Default")
      (node (ref "J9") (pin "3") (pinfunction "TX_3") (pintype "bidirectional"))
      (node (ref "U1") (pin "17") (pinfunction "PA1/ROM-UART-TX_17") (pintype "bidirectional"))
    )
    (net (code "8") (name "GND") (class "Default")
      (node (ref "B1") (pin "2") (pinfunction "GND_2") (pintype "bidirectional"))
      (node (ref "B1") (pin "5") (pinfunction "GND_5") (pintype "bidirectional"))
      (node (ref "B1") (pin "6") (pinfunction "GND_6") (pintype "bidirectional"))
      (node (ref "C1") (pin "2") (pinfunction "2_2") (pintype "bidirectional"))
      (node (ref "C10") (pin "2") (pinfunction "2_2") (pintype "passive"))
      (node (ref "C11") (pin "2") (pinfunction "2_2") (pintype "bidirectional"))
      (node (ref "C12") (pin "2") (pinfunction "2_2") (pintype "bidirectional"))
      (node (ref "C13") (pin "2") (pinfunction "2_2") (pintype "bidirectional"))
      (node (ref "C14") (pin "2") (pinfunction "2_2") (pintype "bidirectional"))
      (node (ref "C15") (pin "2") (pinfunction "2_2") (pintype "bidirectional"))
      (node (ref "C16") (pin "2") (pinfunction "2_2") (pintype "bidirectional"))
      (node (ref "C17") (pin "2") (pinfunction "2_2") (pintype "bidirectional"))
      (node (ref "C18") (pin "2") (pinfunction "2_2") (pintype "bidirectional"))
      (node (ref "C19") (pin "2") (pinfunction "2_2") (pintype "bidirectional"))
      (node (ref "C2") (pin "2") (pinfunction "2_2") (pintype "bidirectional"))
      (node (ref "C20") (pin "2") (pinfunction "2_2") (pintype "passive"))
      (node (ref "C21") (pin "2") (pinfunction "2_2") (pintype "passive"))
      (node (ref "C22") (pin "2") (pinfunction "2_2") (pintype "passive"))
      (node (ref "C24") (pin "2") (pinfunction "2_2") (pintype "passive"))
      (node (ref "C25") (pin "2") (pinfunction "2_2") (pintype "bidirectional"))
      (node (ref "C26") (pin "2") (pinfunction "2_2") (pintype "bidirectional"))
      (node (ref "C27") (pin "2") (pinfunction "2_2") (pintype "bidirectional"))
      (node (ref "C28") (pin "2") (pinfunction "2_2") (pintype "passive"))
      (node (ref "C29") (pin "2") (pinfunction "2_2") (pintype "passive"))
      (node (ref "C3") (pin "2") (pinfunction "2_2") (pintype "bidirectional"))
      (node (ref "C30") (pin "2") (pinfunction "2_2") (pintype "passive"))
      (node (ref "C31") (pin "2") (pinfunction "2_2") (pintype "passive"))
      (node (ref "C32") (pin "2") (pinfunction "2_2") (pintype "passive"))
      (node (ref "C33") (pin "2") (pinfunction "2_2") (pintype "passive"))
      (node (ref "C34") (pin "-") (pinfunction "-_-") (pintype "bidirectional"))
      (node (ref "C4") (pin "2") (pinfunction "2_2") (pintype "bidirectional"))
      (node (ref "C5") (pin "2") (pinfunction "2_2") (pintype "passive"))
      (node (ref "C6") (pin "2") (pinfunction "2_2") (pintype "passive"))
      (node (ref "C7") (pin "2") (pinfunction "2_2") (pintype "bidirectional"))
      (node (ref "C8") (pin "2") (pinfunction "2_2") (pintype "passive"))
      (node (ref "C9") (pin "2") (pinfunction "2_2") (pintype "passive"))
      (node (ref "J9") (pin "2") (pinfunction "GND_2") (pintype "bidirectional"))
      (node (ref "L4") (pin "P$2") (pinfunction "P$2_P$2") (pintype "bidirectional"))
      (node (ref "Q2") (pin "2") (pinfunction "S_2") (pintype "bidirectional"))
      (node (ref "R14") (pin "1") (pinfunction "1_1") (pintype "passive"))
      (node (ref "R16") (pin "1") (pinfunction "1_1") (pintype "passive"))
      (node (ref "R17") (pin "2") (pinfunction "2_2") (pintype "passive"))
      (node (ref "R21") (pin "1") (pinfunction "1_1") (pintype "passive"))
      (node (ref "R9") (pin "1") (pinfunction "1_1") (pintype "passive"))
      (node (ref "TP1") (pin "TESTPOINT") (pinfunction "TESTPOINT_TESTPOINT") (pintype "bidirectional"))
      (node (ref "U1") (pin "VSS_QFN") (pinfunction "GND_VSS_QFN") (pintype "bidirectional"))
      (node (ref "U2") (pin "4") (pinfunction "VSS_4") (pintype "bidirectional"))
      (node (ref "U3") (pin "10") (pinfunction "DGND_10") (pintype "bidirectional"))
      (node (ref "U3") (pin "8") (pinfunction "AGND_8") (pintype "bidirectional"))
      (node (ref "U4") (pin "7") (pinfunction "GND_7") (pintype "bidirectional"))
      (node (ref "U4") (pin "THERMALPAD") (pinfunction "GND_THERMALPAD") (pintype "bidirectional"))
      (node (ref "U5") (pin "2") (pinfunction "~{EN}_2") (pintype "bidirectional"))
      (node (ref "U5") (pin "3") (pinfunction "GND_3") (pintype "bidirectional"))
      (node (ref "U5") (pin "PAD") (pinfunction "GND_PAD") (pintype "bidirectional"))
      (node (ref "U6") (pin "3") (pinfunction "GND_3") (pintype "bidirectional"))
      (node (ref "X1") (pin "2") (pinfunction "GND_2") (pintype "bidirectional"))
      (node (ref "X1") (pin "4") (pinfunction "GND_4") (pintype "bidirectional"))
    )
    (net (code "9") (name "LOAD_NEUTRAL") (class "Default")
      (node (ref "J4") (pin "P$1") (pinfunction "P$1_P$1") (pintype "bidirectional"))
      (node (ref "L3") (pin "P$1") (pinfunction "P$1_P$1") (pintype "bidirectional"))
      (node (ref "R1") (pin "2") (pinfunction "2_2") (pintype "passive"))
    )
    (net (code "10") (name "LOAD_PHASE") (class "Default")
      (node (ref "J3") (pin "P$1") (pinfunction "P$1_P$1") (pintype "bidirectional"))
      (node (ref "K1") (pin "1") (pinfunction "1_1") (pintype "bidirectional"))
    )
    (net (code "11") (name "MISO") (class "Default")
      (node (ref "TP3") (pin "TESTPOINT") (pinfunction "TESTPOINT_TESTPOINT") (pintype "bidirectional"))
      (node (ref "U1") (pin "9") (pinfunction "PC4_9") (pintype "bidirectional"))
      (node (ref "U2") (pin "2") (pinfunction "SO_2") (pintype "bidirectional"))
      (node (ref "U4") (pin "4") (pinfunction "A3_4") (pintype "bidirectional"))
    )
    (net (code "12") (name "MISO_5V") (class "Default")
      (node (ref "U3") (pin "19") (pinfunction "DOUT_19") (pintype "bidirectional"))
      (node (ref "U4") (pin "11") (pinfunction "B3_11") (pintype "bidirectional"))
    )
    (net (code "13") (name "MOSI") (class "Default")
      (node (ref "TP2") (pin "TESTPOINT") (pinfunction "TESTPOINT_TESTPOINT") (pintype "bidirectional"))
      (node (ref "U1") (pin "11") (pinfunction "PC3_11") (pintype "bidirectional"))
      (node (ref "U2") (pin "5") (pinfunction "SI_5") (pintype "bidirectional"))
      (node (ref "U4") (pin "5") (pinfunction "A4_5") (pintype "bidirectional"))
    )
    (net (code "14") (name "MOSI_5V") (class "Default")
      (node (ref "U3") (pin "20") (pinfunction "DIN_20") (pintype "bidirectional"))
      (node (ref "U4") (pin "10") (pinfunction "B4_10") (pintype "bidirectional"))
    )
    (net (code "15") (name "Net-(A1-ANTENNA)") (class "Default")
      (node (ref "A1") (pin "1") (pinfunction "ANTENNA_1") (pintype "bidirectional"))
      (node (ref "B1") (pin "1") (pinfunction "ANT_1") (pintype "bidirectional"))
    )
    (net (code "16") (name "Net-(B1-BAL_N)") (class "Default")
      (node (ref "B1") (pin "3") (pinfunction "BAL_N_3") (pintype "bidirectional"))
      (node (ref "U1") (pin "38") (pinfunction "RF_N_38") (pintype "bidirectional"))
    )
    (net (code "17") (name "Net-(B1-BAL_P)") (class "Default")
      (node (ref "B1") (pin "4") (pinfunction "BAL_P_4") (pintype "bidirectional"))
      (node (ref "U1") (pin "37") (pinfunction "RF_P_37") (pintype "bidirectional"))
    )
    (net (code "18") (name "Net-(D3-ANNODE)") (class "Default")
      (node (ref "D3") (pin "1") (pinfunction "ANNODE_1") (pintype "bidirectional"))
      (node (ref "K1") (pin "4") (pinfunction "4_4") (pintype "bidirectional"))
      (node (ref "Q2") (pin "3") (pinfunction "D_3") (pintype "bidirectional"))
    )
    (net (code "19") (name "Net-(D3-CATHODE)") (class "Default")
      (node (ref "D3") (pin "3") (pinfunction "CATHODE_3") (pintype "bidirectional"))
      (node (ref "K1") (pin "3") (pinfunction "3_3") (pintype "bidirectional"))
      (node (ref "R3") (pin "1") (pinfunction "1_1") (pintype "passive"))
    )
    (net (code "20") (name "Net-(D4-PadA)") (class "Default")
      (node (ref "D4") (pin "A") (pinfunction "A_A") (pintype "passive"))
      (node (ref "R4") (pin "2") (pinfunction "2_2") (pintype "passive"))
    )
    (net (code "21") (name "Net-(D5-PadA)") (class "Default")
      (node (ref "D5") (pin "A") (pinfunction "A_A") (pintype "passive"))
      (node (ref "R5") (pin "2") (pinfunction "2_2") (pintype "passive"))
    )
    (net (code "22") (name "Net-(D6-PadA)") (class "Default")
      (node (ref "D6") (pin "A") (pinfunction "A_A") (pintype "passive"))
      (node (ref "R6") (pin "2") (pinfunction "2_2") (pintype "passive"))
    )
    (net (code "23") (name "Net-(L1-P$2)") (class "Default")
      (node (ref "L1") (pin "2") (pinfunction "P$2_2") (pintype "bidirectional"))
      (node (ref "R22") (pin "1") (pinfunction "1_1") (pintype "passive"))
    )
    (net (code "24") (name "Net-(L2-PadP$2)") (class "Default")
      (node (ref "L2") (pin "P$2") (pinfunction "P$2_P$2") (pintype "bidirectional"))
      (node (ref "R8") (pin "1") (pinfunction "1_1") (pintype "passive"))
    )
    (net (code "25") (name "Net-(L3-PadP$2)") (class "Default")
      (node (ref "L3") (pin "P$2") (pinfunction "P$2_P$2") (pintype "bidirectional"))
      (node (ref "R7") (pin "1") (pinfunction "1_1") (pintype "passive"))
    )
    (net (code "26") (name "Net-(Q1-C)") (class "Default")
      (node (ref "D2") (pin "CATHODE") (pinfunction "CATHODE_CATHODE") (pintype "bidirectional"))
      (node (ref "Q1") (pin "P$2") (pinfunction "C_P$2") (pintype "bidirectional"))
      (node (ref "R20") (pin "2") (pinfunction "2_2") (pintype "passive"))
      (node (ref "R23") (pin "2") (pinfunction "2_2") (pintype "passive"))
    )
    (net (code "27") (name "Net-(Q1-G)") (class "Default")
      (node (ref "Q1") (pin "P$1") (pinfunction "G_P$1") (pintype "bidirectional"))
      (node (ref "U5") (pin "8") (pinfunction "GATE_8") (pintype "bidirectional"))
    )
    (net (code "28") (name "Net-(R20-Pad1)") (class "Default")
      (node (ref "R20") (pin "1") (pinfunction "1_1") (pintype "passive"))
      (node (ref "R21") (pin "2") (pinfunction "2_2") (pintype "passive"))
    )
    (net (code "29") (name "Net-(R23-Pad1)") (class "Default")
      (node (ref "R23") (pin "1") (pinfunction "1_1") (pintype "passive"))
      (node (ref "R24") (pin "2") (pinfunction "2_2") (pintype "passive"))
    )
    (net (code "30") (name "Net-(U1-DCOUPL1)") (class "Default")
      (node (ref "C26") (pin "1") (pinfunction "1_1") (pintype "bidirectional"))
      (node (ref "C27") (pin "1") (pinfunction "1_1") (pintype "bidirectional"))
      (node (ref "U1") (pin "32") (pinfunction "DCOUPL2_32") (pintype "bidirectional"))
      (node (ref "U1") (pin "56") (pinfunction "DCOUPL1_56") (pintype "bidirectional"))
    )
    (net (code "31") (name "Net-(U1-PA6)") (class "Default")
      (node (ref "D5") (pin "C") (pinfunction "C_C") (pintype "passive"))
      (node (ref "U1") (pin "22") (pinfunction "PA6_22") (pintype "bidirectional"))
    )
    (net (code "32") (name "Net-(U1-PA7)") (class "Default")
      (node (ref "D4") (pin "C") (pinfunction "C_C") (pintype "passive"))
      (node (ref "U1") (pin "23") (pinfunction "PA7_23") (pintype "bidirectional"))
    )
    (net (code "33") (name "Net-(U1-PD6{slash}XOSC32K_Q1)") (class "Default")
      (node (ref "C3") (pin "1") (pinfunction "1_1") (pintype "bidirectional"))
      (node (ref "U1") (pin "44") (pinfunction "PD6/XOSC32K_Q1_44") (pintype "bidirectional"))
      (node (ref "X2") (pin "1") (pinfunction "1_1") (pintype "bidirectional"))
    )
    (net (code "34") (name "Net-(U1-PD7{slash}XOSC32K_Q2)") (class "Default")
      (node (ref "C4") (pin "1") (pinfunction "1_1") (pintype "bidirectional"))
      (node (ref "U1") (pin "45") (pinfunction "PD7/XOSC32K_Q2_45") (pintype "bidirectional"))
      (node (ref "X2") (pin "2") (pinfunction "2_2") (pintype "bidirectional"))
    )
    (net (code "35") (name "Net-(U1-R_BIAS)") (class "Default")
      (node (ref "R17") (pin "1") (pinfunction "1_1") (pintype "passive"))
      (node (ref "U1") (pin "42") (pinfunction "R_BIAS_42") (pintype "bidirectional"))
    )
    (net (code "36") (name "Net-(U1-XOSC32M_Q1)") (class "Default")
      (node (ref "C1") (pin "1") (pinfunction "1_1") (pintype "bidirectional"))
      (node (ref "U1") (pin "34") (pinfunction "XOSC32M_Q1_34") (pintype "bidirectional"))
      (node (ref "X1") (pin "1") (pinfunction "1_1") (pintype "bidirectional"))
    )
    (net (code "37") (name "Net-(U1-XOSC32M_Q2)") (class "Default")
      (node (ref "C2") (pin "1") (pinfunction "1_1") (pintype "bidirectional"))
      (node (ref "U1") (pin "35") (pinfunction "XOSC32M_Q2_35") (pintype "bidirectional"))
      (node (ref "X1") (pin "3") (pinfunction "2_3") (pintype "bidirectional"))
    )
    (net (code "38") (name "Net-(U1-~{RESET})") (class "Default")
      (node (ref "C18") (pin "1") (pinfunction "1_1") (pintype "bidirectional"))
      (node (ref "R10") (pin "2") (pinfunction "2_2") (pintype "passive"))
      (node (ref "U1") (pin "28") (pinfunction "~{RESET}_28") (pintype "bidirectional"))
    )
    (net (code "39") (name "Net-(U3-AVDD)") (class "Default")
      (node (ref "C21") (pin "1") (pinfunction "1_1") (pintype "passive"))
      (node (ref "C31") (pin "1") (pinfunction "1_1") (pintype "passive"))
      (node (ref "R2") (pin "1") (pinfunction "1_1") (pintype "passive"))
      (node (ref "U3") (pin "3") (pinfunction "AVDD_3") (pintype "bidirectional"))
    )
    (net (code "40") (name "Net-(U3-CLKIN)") (class "Default")
      (node (ref "C6") (pin "1") (pinfunction "1_1") (pintype "passive"))
      (node (ref "U3") (pin "15") (pinfunction "CLKIN_15") (pintype "bidirectional"))
      (node (ref "X3") (pin "1") (pinfunction "P$1_1") (pintype "bidirectional"))
    )
    (net (code "41") (name "Net-(U3-CLKOUT)") (class "Default")
      (node (ref "C5") (pin "1") (pinfunction "1_1") (pintype "passive"))
      (node (ref "U3") (pin "16") (pinfunction "CLKOUT_16") (pintype "bidirectional"))
      (node (ref "X3") (pin "2") (pinfunction "P$2_2") (pintype "bidirectional"))
    )
    (net (code "42") (name "Net-(U3-REF)") (class "Default")
      (node (ref "C22") (pin "1") (pinfunction "1_1") (pintype "passive"))
      (node (ref "C32") (pin "1") (pinfunction "1_1") (pintype "passive"))
      (node (ref "U3") (pin "9") (pinfunction "REF_9") (pintype "bidirectional"))
    )
    (net (code "43") (name "Net-(U5-FB)") (class "Default")
      (node (ref "R16") (pin "2") (pinfunction "2_2") (pintype "passive"))
      (node (ref "R19") (pin "1") (pinfunction "1_1") (pintype "passive"))
      (node (ref "U5") (pin "5") (pinfunction "FB_5") (pintype "bidirectional"))
    )
    (net (code "44") (name "Net-(U5-VGD)") (class "Default")
      (node (ref "C23") (pin "2") (pinfunction "2_2") (pintype "passive"))
      (node (ref "U5") (pin "7") (pinfunction "VGD_7") (pintype "bidirectional"))
    )
    (net (code "45") (name "Net-(U5-VIN)") (class "Default")
      (node (ref "R24") (pin "1") (pinfunction "1_1") (pintype "passive"))
      (node (ref "U5") (pin "1") (pinfunction "VIN_1") (pintype "bidirectional"))
    )
    (net (code "46") (name "RELAY_CTRL") (class "Default")
      (node (ref "Q2") (pin "1") (pinfunction "G_1") (pintype "bidirectional"))
      (node (ref "R18") (pin "2") (pinfunction "2_2") (pintype "passive"))
      (node (ref "U1") (pin "50") (pinfunction "PB5_50") (pintype "bidirectional"))
    )
    (net (code "47") (name "RELAY_LED") (class "Default")
      (node (ref "D6") (pin "C") (pinfunction "C_C") (pintype "passive"))
      (node (ref "U1") (pin "51") (pinfunction "PB4_51") (pintype "bidirectional"))
    )
    (net (code "48") (name "SCLK") (class "Default")
      (node (ref "TP4") (pin "TESTPOINT") (pinfunction "TESTPOINT_TESTPOINT") (pintype "bidirectional"))
      (node (ref "U1") (pin "12") (pinfunction "PC2_12") (pintype "bidirectional"))
      (node (ref "U2") (pin "6") (pinfunction "SCK_6") (pintype "bidirectional"))
      (node (ref "U4") (pin "3") (pinfunction "A2_3") (pintype "bidirectional"))
    )
    (net (code "49") (name "SCLK_5V") (class "Default")
      (node (ref "U3") (pin "18") (pinfunction "SCLK_18") (pintype "bidirectional"))
      (node (ref "U4") (pin "12") (pinfunction "B2_12") (pintype "bidirectional"))
    )
    (net (code "50") (name "TCK") (class "Default")
      (node (ref "TP14") (pin "TP") (pinfunction "TP_TP") (pintype "input"))
      (node (ref "U1") (pin "47") (pinfunction "JTAG_TCK_47") (pintype "bidirectional"))
    )
    (net (code "51") (name "TDO") (class "Default")
      (node (ref "TP13") (pin "TP") (pinfunction "TP_TP") (pintype "input"))
      (node (ref "U1") (pin "48") (pinfunction "PB7/JTAG-TDO_48") (pintype "bidirectional"))
    )
    (net (code "52") (name "TMS") (class "Default")
      (node (ref "TP12") (pin "TP") (pinfunction "TP_TP") (pintype "input"))
      (node (ref "U1") (pin "46") (pinfunction "JTAG_TMS_46") (pintype "bidirectional"))
    )
    (net (code "53") (name "USER_RELAY_CTRL") (class "Default")
      (node (ref "R14") (pin "2") (pinfunction "2_2") (pintype "passive"))
      (node (ref "S1") (pin "P$2") (pinfunction "P$2_P$2") (pintype "passive"))
      (node (ref "S1") (pin "P$4") (pinfunction "P$4_P$4") (pintype "passive"))
      (node (ref "U1") (pin "52") (pinfunction "PB3_52") (pintype "bidirectional"))
    )
    (net (code "54") (name "V1N") (class "Default")
      (node (ref "C9") (pin "1") (pinfunction "1_1") (pintype "passive"))
      (node (ref "R8") (pin "2") (pinfunction "2_2") (pintype "passive"))
      (node (ref "TP10") (pin "TESTPOINT") (pinfunction "TESTPOINT_TESTPOINT") (pintype "bidirectional"))
      (node (ref "U3") (pin "5") (pinfunction "V1N_5") (pintype "bidirectional"))
      (node (ref "U3") (pin "6") (pinfunction "V2N_6") (pintype "bidirectional"))
    )
    (net (code "55") (name "V1P") (class "Default")
      (node (ref "C8") (pin "1") (pinfunction "1_1") (pintype "passive"))
      (node (ref "R7") (pin "2") (pinfunction "2_2") (pintype "passive"))
      (node (ref "TP9") (pin "TESTPOINT") (pinfunction "TESTPOINT_TESTPOINT") (pintype "bidirectional"))
      (node (ref "U3") (pin "4") (pinfunction "V1P_4") (pintype "bidirectional"))
    )
    (net (code "56") (name "V2P") (class "Default")
      (node (ref "C10") (pin "1") (pinfunction "1_1") (pintype "passive"))
      (node (ref "R22") (pin "2") (pinfunction "2_2") (pintype "passive"))
      (node (ref "R9") (pin "2") (pinfunction "2_2") (pintype "passive"))
      (node (ref "TP11") (pin "TESTPOINT") (pinfunction "TESTPOINT_TESTPOINT") (pintype "bidirectional"))
      (node (ref "U3") (pin "7") (pinfunction "V2P_7") (pintype "bidirectional"))
    )
    (net (code "57") (name "VDC") (class "Default")
      (node (ref "C23") (pin "1") (pinfunction "1_1") (pintype "passive"))
      (node (ref "C28") (pin "1") (pinfunction "1_1") (pintype "passive"))
      (node (ref "C29") (pin "1") (pinfunction "1_1") (pintype "passive"))
      (node (ref "C34") (pin "+") (pinfunction "+_+") (pintype "bidirectional"))
      (node (ref "Q1") (pin "P$3") (pinfunction "E_P$3") (pintype "bidirectional"))
      (node (ref "R19") (pin "2") (pinfunction "2_2") (pintype "passive"))
      (node (ref "U5") (pin "6") (pinfunction "VOUT_6") (pintype "bidirectional"))
      (node (ref "U6") (pin "8") (pinfunction "VIN_8") (pintype "bidirectional"))
    )
    (net (code "58") (name "WALL_NEUTRAL") (class "Default")
      (node (ref "D1") (pin "CATHODE") (pinfunction "P$2_CATHODE") (pintype "bidirectional"))
      (node (ref "J5") (pin "NEUTRAL1") (pinfunction "NEUTRAL_NEUTRAL1") (pintype "bidirectional"))
      (node (ref "J5") (pin "NEUTRAL2") (pinfunction "NEUTRAL_NEUTRAL2") (pintype "bidirectional"))
      (node (ref "L2") (pin "P$1") (pinfunction "P$1_P$1") (pintype "bidirectional"))
      (node (ref "L4") (pin "P$1") (pinfunction "P$1_P$1") (pintype "bidirectional"))
      (node (ref "R1") (pin "1") (pinfunction "1_1") (pintype "passive"))
    )
    (net (code "59") (name "WALL_PHASE") (class "Default")
      (node (ref "D1") (pin "ANODE") (pinfunction "P$1_ANODE") (pintype "bidirectional"))
      (node (ref "D2") (pin "ANNODE") (pinfunction "ANNODE_ANNODE") (pintype "bidirectional"))
      (node (ref "J5") (pin "PHASE1") (pinfunction "PHASE_PHASE1") (pintype "bidirectional"))
      (node (ref "J5") (pin "PHASE2") (pinfunction "PHASE_PHASE2") (pintype "bidirectional"))
      (node (ref "K1") (pin "2") (pinfunction "2_2") (pintype "bidirectional"))
      (node (ref "L1") (pin "1") (pinfunction "P$1_1") (pintype "bidirectional"))
    )
    (net (code "60") (name "unconnected-(J1-P$1-Pad1)") (class "Default")
      (node (ref "J1") (pin "1") (pinfunction "P$1_1") (pintype "bidirectional"))
    )
    (net (code "61") (name "unconnected-(J6-P$1-Pad1)") (class "Default")
      (node (ref "J6") (pin "1") (pinfunction "P$1_1") (pintype "bidirectional"))
    )
    (net (code "62") (name "unconnected-(J7-P$1-Pad1)") (class "Default")
      (node (ref "J7") (pin "1") (pinfunction "P$1_1") (pintype "bidirectional"))
    )
    (net (code "63") (name "unconnected-(J8-P$1-Pad1)") (class "Default")
      (node (ref "J8") (pin "1") (pinfunction "P$1_1") (pintype "bidirectional"))
    )
    (net (code "64") (name "unconnected-(U1-DGND_USB-Pad1)") (class "Default")
      (node (ref "U1") (pin "1") (pinfunction "DGND_USB_1") (pintype "bidirectional"))
    )
    (net (code "65") (name "unconnected-(U1-DVDD_USB-Pad4)") (class "Default")
      (node (ref "U1") (pin "4") (pinfunction "DVDD_USB_4") (pintype "bidirectional"))
    )
    (net (code "66") (name "unconnected-(U1-PA3{slash}ROM-SSI-SEL-Pad19)") (class "Default")
      (node (ref "U1") (pin "19") (pinfunction "PA3/ROM-SSI-SEL_19") (pintype "bidirectional"))
    )
    (net (code "67") (name "unconnected-(U1-PA4{slash}ROM-SSI-RX-Pad20)") (class "Default")
      (node (ref "U1") (pin "20") (pinfunction "PA4/ROM-SSI-RX_20") (pintype "bidirectional"))
    )
    (net (code "68") (name "unconnected-(U1-PA5{slash}ROM-SSI-TX-Pad21)") (class "Default")
      (node (ref "U1") (pin "21") (pinfunction "PA5/ROM-SSI-TX_21") (pintype "bidirectional"))
    )
    (net (code "69") (name "unconnected-(U1-PB6{slash}JTAG-TDI-Pad49)") (class "Default")
      (node (ref "U1") (pin "49") (pinfunction "PB6/JTAG-TDI_49") (pintype "bidirectional"))
    )
    (net (code "70") (name "unconnected-(U1-PC0-Pad14)") (class "Default")
      (node (ref "U1") (pin "14") (pinfunction "PC0_14") (pintype "bidirectional"))
    )
    (net (code "71") (name "unconnected-(U1-PD0-Pad25)") (class "Default")
      (node (ref "U1") (pin "25") (pinfunction "PD0_25") (pintype "bidirectional"))
    )
    (net (code "72") (name "unconnected-(U1-PD1-Pad26)") (class "Default")
      (node (ref "U1") (pin "26") (pinfunction "PD1_26") (pintype "bidirectional"))
    )
    (net (code "73") (name "unconnected-(U1-PD2-Pad27)") (class "Default")
      (node (ref "U1") (pin "27") (pinfunction "PD2_27") (pintype "bidirectional"))
    )
    (net (code "74") (name "unconnected-(U1-PD3-Pad29)") (class "Default")
      (node (ref "U1") (pin "29") (pinfunction "PD3_29") (pintype "bidirectional"))
    )
    (net (code "75") (name "unconnected-(U1-PD4-Pad30)") (class "Default")
      (node (ref "U1") (pin "30") (pinfunction "PD4_30") (pintype "bidirectional"))
    )
    (net (code "76") (name "unconnected-(U1-PD5-Pad31)") (class "Default")
      (node (ref "U1") (pin "31") (pinfunction "PD5_31") (pintype "bidirectional"))
    )
    (net (code "77") (name "unconnected-(U1-USB_N-Pad3)") (class "Default")
      (node (ref "U1") (pin "3") (pinfunction "USB_N_3") (pintype "bidirectional"))
    )
    (net (code "78") (name "unconnected-(U1-USB_P-Pad2)") (class "Default")
      (node (ref "U1") (pin "2") (pinfunction "USB_P_2") (pintype "bidirectional"))
    )
    (net (code "79") (name "unconnected-(U3-~{SAG}-Pad13)") (class "Default")
      (node (ref "U3") (pin "13") (pinfunction "~{SAG}_13") (pintype "bidirectional"))
    )
    (net (code "80") (name "~{ADE_CS_5V}") (class "Default")
      (node (ref "U3") (pin "17") (pinfunction "~{CS}_17") (pintype "bidirectional"))
      (node (ref "U4") (pin "13") (pinfunction "B1_13") (pintype "bidirectional"))
    )
    (net (code "81") (name "~{ADE_CS}") (class "Default")
      (node (ref "TP5") (pin "TESTPOINT") (pinfunction "TESTPOINT_TESTPOINT") (pintype "bidirectional"))
      (node (ref "U1") (pin "53") (pinfunction "PB2_53") (pintype "bidirectional"))
      (node (ref "U4") (pin "2") (pinfunction "A1_2") (pintype "bidirectional"))
    )
    (net (code "82") (name "~{ADE_IRQ}") (class "Default")
      (node (ref "TP6") (pin "TESTPOINT") (pinfunction "TESTPOINT_TESTPOINT") (pintype "bidirectional"))
      (node (ref "U1") (pin "54") (pinfunction "PB1_54") (pintype "bidirectional"))
      (node (ref "U3") (pin "14") (pinfunction "~{IRQ}_14") (pintype "bidirectional"))
    )
    (net (code "83") (name "~{ADE_RESET}") (class "Default")
      (node (ref "R15") (pin "2") (pinfunction "2_2") (pintype "passive"))
      (node (ref "U3") (pin "1") (pinfunction "~{RESET}_1") (pintype "bidirectional"))
    )
    (net (code "84") (name "~{FRAM_CS}") (class "Default")
      (node (ref "R11") (pin "1") (pinfunction "1_1") (pintype "passive"))
      (node (ref "U1") (pin "8") (pinfunction "PC5_8") (pintype "bidirectional"))
      (node (ref "U2") (pin "1") (pinfunction "~{CS}_1") (pintype "bidirectional"))
    )
    (net (code "85") (name "~{FRAM_HOLD}") (class "Default")
      (node (ref "R12") (pin "1") (pinfunction "1_1") (pintype "passive"))
      (node (ref "U1") (pin "13") (pinfunction "PC1_13") (pintype "bidirectional"))
      (node (ref "U2") (pin "7") (pinfunction "~{HOLD}_7") (pintype "bidirectional"))
    )
    (net (code "86") (name "~{FRAM_WP}") (class "Default")
      (node (ref "R13") (pin "1") (pinfunction "1_1") (pintype "passive"))
      (node (ref "U1") (pin "7") (pinfunction "PC6_7") (pintype "bidirectional"))
      (node (ref "U2") (pin "3") (pinfunction "~{WP}_3") (pintype "bidirectional"))
    )
    (net (code "87") (name "~{RESET}") (class "Default")
      (node (ref "J9") (pin "6") (pinfunction "~{RESET}_6") (pintype "bidirectional"))
      (node (ref "R10") (pin "1") (pinfunction "1_1") (pintype "passive"))
    )
  )
)
